# ecohydro-mega-shield.net
KiCad netlist of a schematic drawn in EAGLE
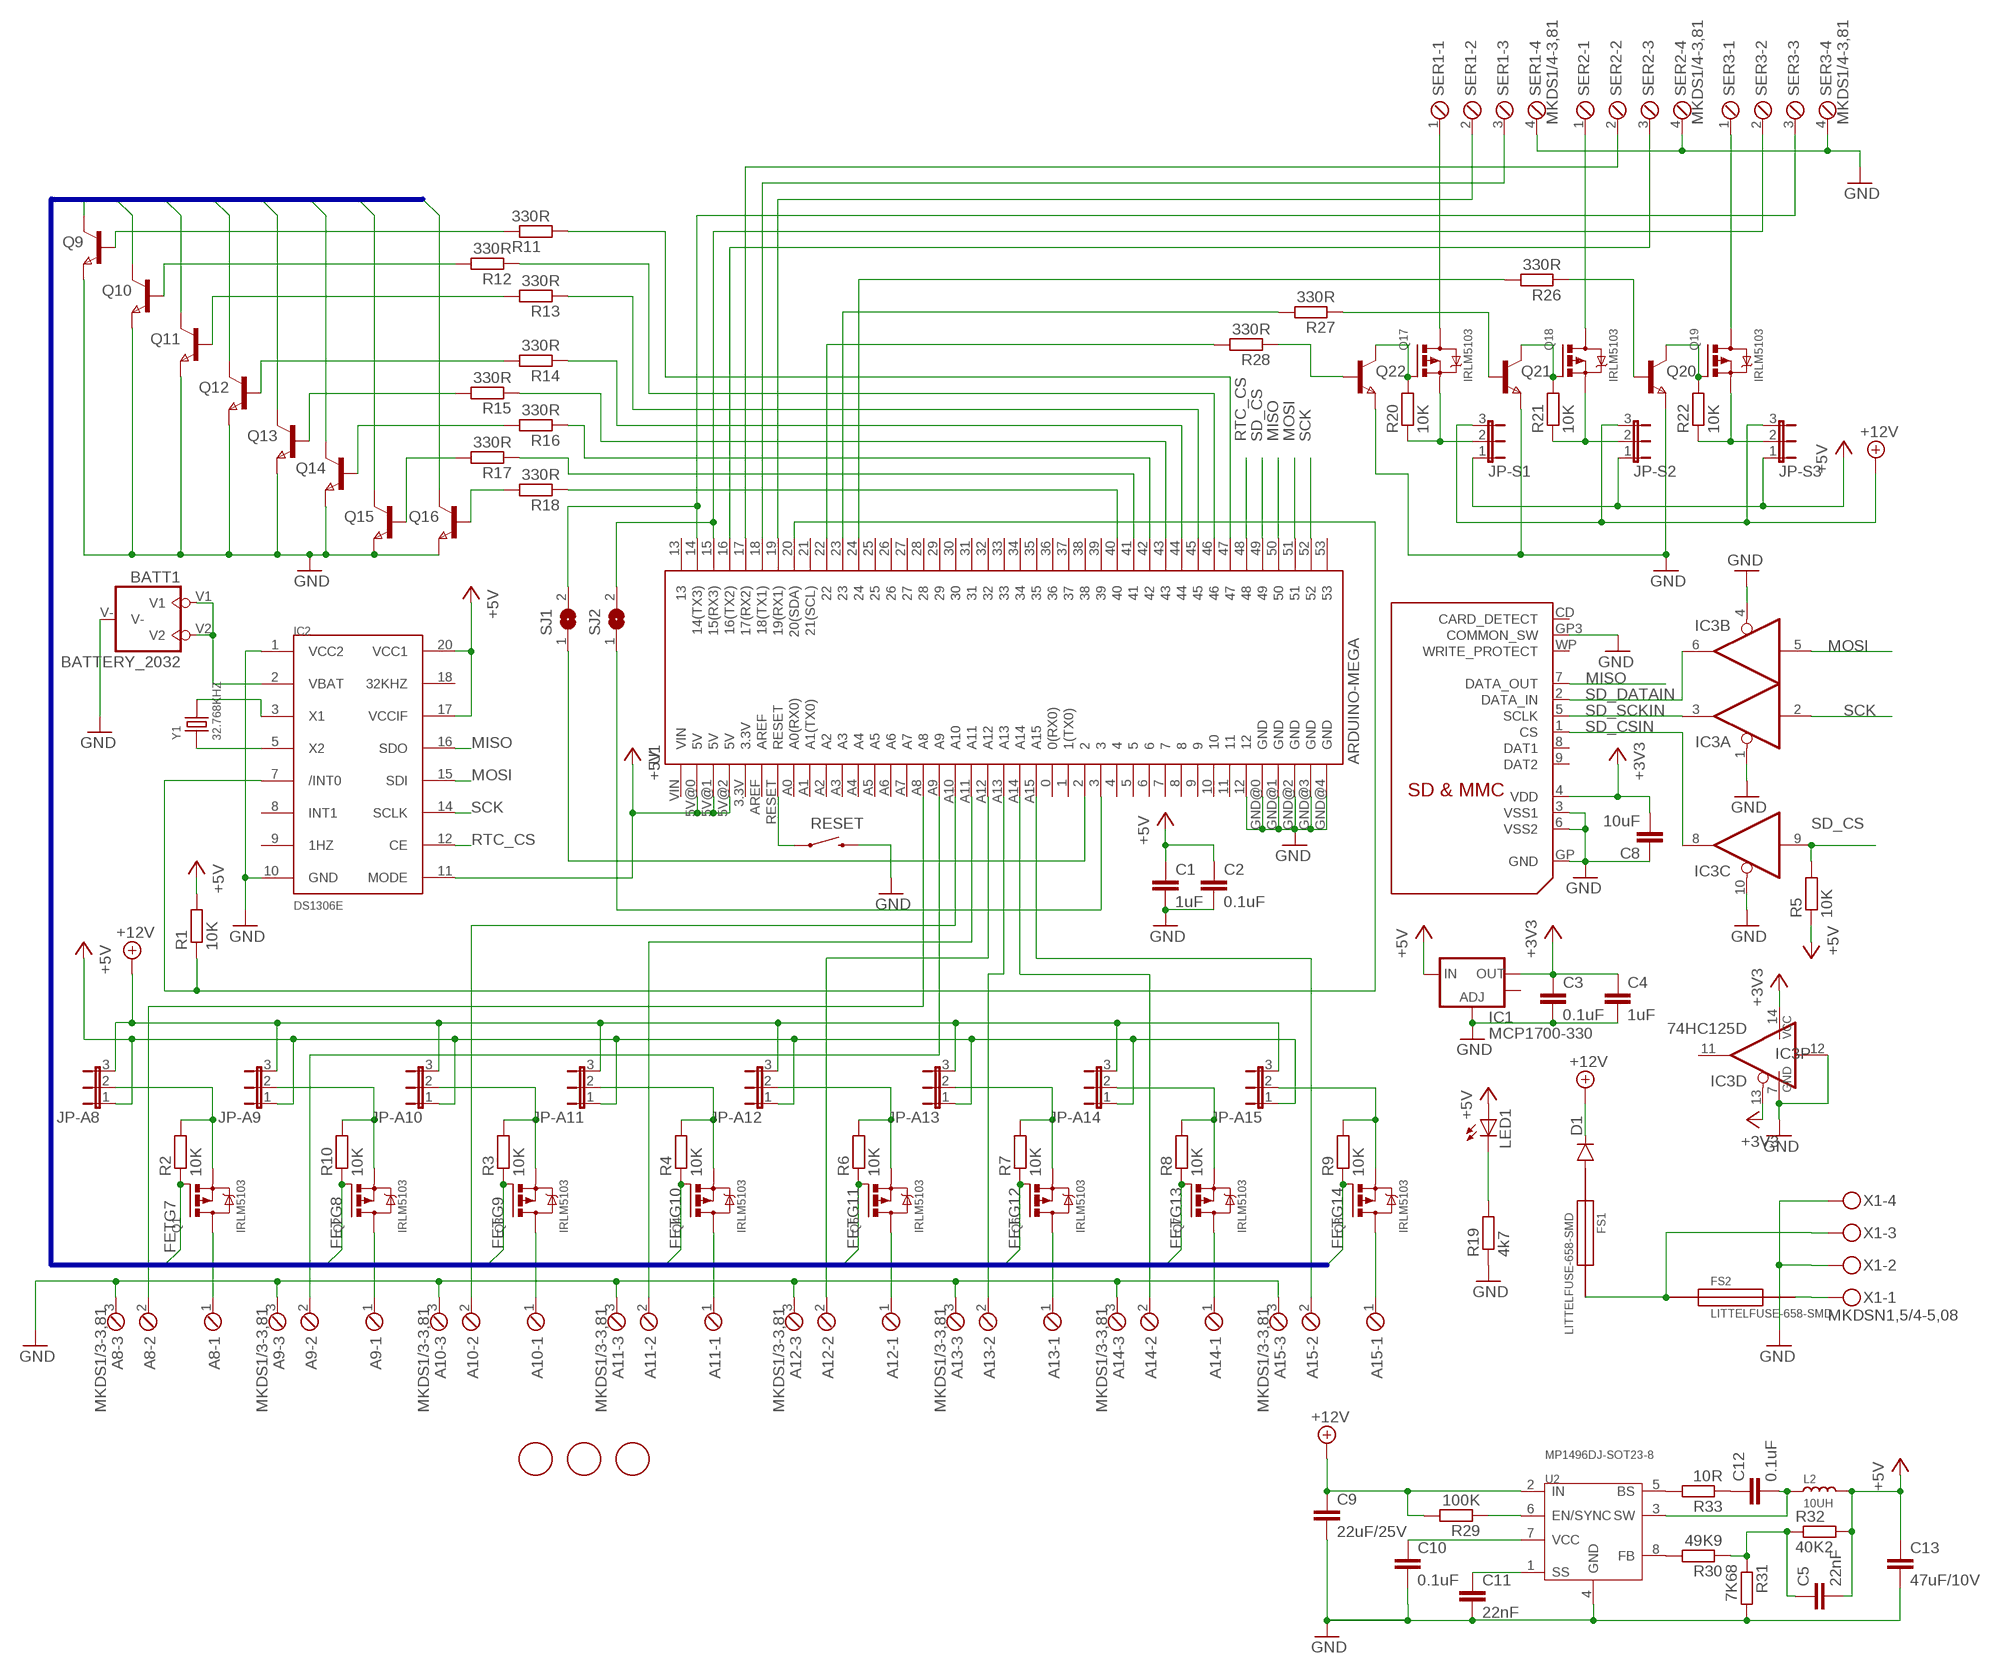
[diagram p0: schematic, sheet 1]

(export (version "E")
  (design (tool "Eeschema 10.0.6"))
  (components
    (comp (ref "A8")
      (value "MKDS1/3-3,81")
      (footprint "eagle-import:3POL381")
      (libsource (lib "eagle-import") (part "MKDS1/3-3,81"))
    )
    (comp (ref "A9")
      (value "MKDS1/3-3,81")
      (footprint "eagle-import:3POL381")
      (libsource (lib "eagle-import") (part "MKDS1/3-3,81"))
    )
    (comp (ref "A10")
      (value "MKDS1/3-3,81")
      (footprint "eagle-import:3POL381")
      (libsource (lib "eagle-import") (part "MKDS1/3-3,81"))
    )
    (comp (ref "A11")
      (value "MKDS1/3-3,81")
      (footprint "eagle-import:3POL381")
      (libsource (lib "eagle-import") (part "MKDS1/3-3,81"))
    )
    (comp (ref "A12")
      (value "MKDS1/3-3,81")
      (footprint "eagle-import:3POL381")
      (libsource (lib "eagle-import") (part "MKDS1/3-3,81"))
    )
    (comp (ref "A13")
      (value "MKDS1/3-3,81")
      (footprint "eagle-import:3POL381")
      (libsource (lib "eagle-import") (part "MKDS1/3-3,81"))
    )
    (comp (ref "A14")
      (value "MKDS1/3-3,81")
      (footprint "eagle-import:3POL381")
      (libsource (lib "eagle-import") (part "MKDS1/3-3,81"))
    )
    (comp (ref "A15")
      (value "MKDS1/3-3,81")
      (footprint "eagle-import:3POL381")
      (libsource (lib "eagle-import") (part "MKDS1/3-3,81"))
    )
    (comp (ref "BATT1")
      (value "BATTERY_2032")
      (footprint "eagle-import:BATT2032")
      (libsource (lib "eagle-import") (part "BATTERY_2032"))
    )
    (comp (ref "C1")
      (value "1uF")
      (footprint "eagle-import:C0805K")
      (libsource (lib "eagle-import") (part "C-EUC0805K"))
    )
    (comp (ref "C2")
      (value "0.1uF")
      (footprint "eagle-import:C0805K")
      (libsource (lib "eagle-import") (part "C-EUC0805K"))
    )
    (comp (ref "C3")
      (value "0.1uF")
      (footprint "eagle-import:C0805K")
      (libsource (lib "eagle-import") (part "C-EUC0805K"))
    )
    (comp (ref "C4")
      (value "1uF")
      (footprint "eagle-import:C0805K")
      (libsource (lib "eagle-import") (part "C-EUC0805K"))
    )
    (comp (ref "C5")
      (value "22nF")
      (footprint "eagle-import:C0805K")
      (libsource (lib "eagle-import") (part "C-EUC0805K"))
    )
    (comp (ref "C8")
      (value "10uF")
      (footprint "eagle-import:C0805K")
      (libsource (lib "eagle-import") (part "C-EUC0805K"))
    )
    (comp (ref "C9")
      (value "22uF/25V")
      (footprint "eagle-import:C0805K")
      (libsource (lib "eagle-import") (part "C-EUC0805K"))
    )
    (comp (ref "C10")
      (value "0.1uF")
      (footprint "eagle-import:C0805K")
      (libsource (lib "eagle-import") (part "C-EUC0805K"))
    )
    (comp (ref "C11")
      (value "22nF")
      (footprint "eagle-import:C0805K")
      (libsource (lib "eagle-import") (part "C-EUC0805K"))
    )
    (comp (ref "C12")
      (value "0.1uF")
      (footprint "eagle-import:C0805K")
      (libsource (lib "eagle-import") (part "C-EUC0805K"))
    )
    (comp (ref "C13")
      (value "47uF/10V")
      (footprint "eagle-import:C0805K")
      (libsource (lib "eagle-import") (part "C-EUC0805K"))
    )
    (comp (ref "D1")
      (value "DIODESMA")
      (footprint "eagle-import:SMA-DIODE")
      (libsource (lib "eagle-import") (part "DIODESMA"))
    )
    (comp (ref "FS1")
      (value "LITTELFUSE-658-SMD")
      (footprint "eagle-import:LITTELFUSE-658-SMD")
      (libsource (lib "eagle-import") (part "LITTELFUSE-658-SMD"))
    )
    (comp (ref "FS2")
      (value "LITTELFUSE-658-SMD")
      (footprint "eagle-import:LITTELFUSE-658-SMD")
      (libsource (lib "eagle-import") (part "LITTELFUSE-658-SMD"))
    )
    (comp (ref "IC1")
      (value "MCP1700-330")
      (footprint "eagle-import:SOT223")
      (libsource (lib "eagle-import") (part "V_REG_LM1117SOT223"))
    )
    (comp (ref "IC2")
      (value "DS1306E")
      (footprint "eagle-import:SSOP20")
      (libsource (lib "eagle-import") (part "DS1306E"))
    )
    (comp (ref "IC3")
      (value "74HC125D")
      (footprint "eagle-import:SO14")
      (fields (field (name "DIGIKEY") "568-1392-2-ND "))
      (libsource (lib "eagle-import") (part "74125DHC"))
    )
    (comp (ref "JP-A8")
      (value "JP2E")
      (footprint "eagle-import:JP2")
      (libsource (lib "eagle-import") (part "JP2E"))
    )
    (comp (ref "JP-A9")
      (value "JP2E")
      (footprint "eagle-import:JP2")
      (libsource (lib "eagle-import") (part "JP2E"))
    )
    (comp (ref "JP-A10")
      (value "JP2E")
      (footprint "eagle-import:JP2")
      (libsource (lib "eagle-import") (part "JP2E"))
    )
    (comp (ref "JP-A11")
      (value "JP2E")
      (footprint "eagle-import:JP2")
      (libsource (lib "eagle-import") (part "JP2E"))
    )
    (comp (ref "JP-A12")
      (value "JP2E")
      (footprint "eagle-import:JP2")
      (libsource (lib "eagle-import") (part "JP2E"))
    )
    (comp (ref "JP-A13")
      (value "JP2E")
      (footprint "eagle-import:JP2")
      (libsource (lib "eagle-import") (part "JP2E"))
    )
    (comp (ref "JP-A14")
      (value "JP2E")
      (footprint "eagle-import:JP2")
      (libsource (lib "eagle-import") (part "JP2E"))
    )
    (comp (ref "JP-A15")
      (value "JP2E")
      (footprint "eagle-import:JP2")
      (libsource (lib "eagle-import") (part "JP2E"))
    )
    (comp (ref "JP-S1")
      (value "JP2E")
      (footprint "eagle-import:JP2")
      (libsource (lib "eagle-import") (part "JP2E"))
    )
    (comp (ref "JP-S2")
      (value "JP2E")
      (footprint "eagle-import:JP2")
      (libsource (lib "eagle-import") (part "JP2E"))
    )
    (comp (ref "JP-S3")
      (value "JP2E")
      (footprint "eagle-import:JP2")
      (libsource (lib "eagle-import") (part "JP2E"))
    )
    (comp (ref "L2")
      (value "10UH")
      (footprint "eagle-import:SMD-2P-L6.0XW6.0XH3.0MM")
      (fields (field (name "MPN") "CSAB0630-100M"))
      (libsource (lib "eagle-import") (part "SMD-INDUCTOR-10UH-20%(2P-6X6MM)'0630'"))
    )
    (comp (ref "LED1")
      (value "LED1206")
      (footprint "eagle-import:LED-1206")
      (libsource (lib "eagle-import") (part "LED1206"))
    )
    (comp (ref "Q1")
      (value "IRLM5103")
      (footprint "eagle-import:MICRO3")
      (libsource (lib "eagle-import") (part "IRLM5103"))
    )
    (comp (ref "Q2")
      (value "IRLM5103")
      (footprint "eagle-import:MICRO3")
      (libsource (lib "eagle-import") (part "IRLM5103"))
    )
    (comp (ref "Q3")
      (value "IRLM5103")
      (footprint "eagle-import:MICRO3")
      (libsource (lib "eagle-import") (part "IRLM5103"))
    )
    (comp (ref "Q4")
      (value "IRLM5103")
      (footprint "eagle-import:MICRO3")
      (libsource (lib "eagle-import") (part "IRLM5103"))
    )
    (comp (ref "Q5")
      (value "IRLM5103")
      (footprint "eagle-import:MICRO3")
      (libsource (lib "eagle-import") (part "IRLM5103"))
    )
    (comp (ref "Q6")
      (value "IRLM5103")
      (footprint "eagle-import:MICRO3")
      (libsource (lib "eagle-import") (part "IRLM5103"))
    )
    (comp (ref "Q7")
      (value "IRLM5103")
      (footprint "eagle-import:MICRO3")
      (libsource (lib "eagle-import") (part "IRLM5103"))
    )
    (comp (ref "Q8")
      (value "IRLM5103")
      (footprint "eagle-import:MICRO3")
      (libsource (lib "eagle-import") (part "IRLM5103"))
    )
    (comp (ref "Q9")
      (value "PBSS4021NT,215")
      (footprint "eagle-import:SOT23")
      (libsource (lib "eagle-import") (part "PBSS4021NT,215"))
    )
    (comp (ref "Q10")
      (value "PBSS4021NT,215")
      (footprint "eagle-import:SOT23")
      (libsource (lib "eagle-import") (part "PBSS4021NT,215"))
    )
    (comp (ref "Q11")
      (value "PBSS4021NT,215")
      (footprint "eagle-import:SOT23")
      (libsource (lib "eagle-import") (part "PBSS4021NT,215"))
    )
    (comp (ref "Q12")
      (value "PBSS4021NT,215")
      (footprint "eagle-import:SOT23")
      (libsource (lib "eagle-import") (part "PBSS4021NT,215"))
    )
    (comp (ref "Q13")
      (value "PBSS4021NT,215")
      (footprint "eagle-import:SOT23")
      (libsource (lib "eagle-import") (part "PBSS4021NT,215"))
    )
    (comp (ref "Q14")
      (value "PBSS4021NT,215")
      (footprint "eagle-import:SOT23")
      (libsource (lib "eagle-import") (part "PBSS4021NT,215"))
    )
    (comp (ref "Q15")
      (value "PBSS4021NT,215")
      (footprint "eagle-import:SOT23")
      (libsource (lib "eagle-import") (part "PBSS4021NT,215"))
    )
    (comp (ref "Q16")
      (value "PBSS4021NT,215")
      (footprint "eagle-import:SOT23")
      (libsource (lib "eagle-import") (part "PBSS4021NT,215"))
    )
    (comp (ref "Q17")
      (value "IRLM5103")
      (footprint "eagle-import:MICRO3")
      (libsource (lib "eagle-import") (part "IRLM5103"))
    )
    (comp (ref "Q18")
      (value "IRLM5103")
      (footprint "eagle-import:MICRO3")
      (libsource (lib "eagle-import") (part "IRLM5103"))
    )
    (comp (ref "Q19")
      (value "IRLM5103")
      (footprint "eagle-import:MICRO3")
      (libsource (lib "eagle-import") (part "IRLM5103"))
    )
    (comp (ref "Q20")
      (value "PBSS4021NT,215")
      (footprint "eagle-import:SOT23")
      (libsource (lib "eagle-import") (part "PBSS4021NT,215"))
    )
    (comp (ref "Q21")
      (value "PBSS4021NT,215")
      (footprint "eagle-import:SOT23")
      (libsource (lib "eagle-import") (part "PBSS4021NT,215"))
    )
    (comp (ref "Q22")
      (value "PBSS4021NT,215")
      (footprint "eagle-import:SOT23")
      (libsource (lib "eagle-import") (part "PBSS4021NT,215"))
    )
    (comp (ref "R1")
      (value "10K")
      (footprint "eagle-import:M0805")
      (libsource (lib "eagle-import") (part "rcl_R-EU_M0805"))
    )
    (comp (ref "R2")
      (value "10K")
      (footprint "eagle-import:M0805")
      (libsource (lib "eagle-import") (part "rcl_R-EU_M0805"))
    )
    (comp (ref "R3")
      (value "10K")
      (footprint "eagle-import:M0805")
      (libsource (lib "eagle-import") (part "rcl_R-EU_M0805"))
    )
    (comp (ref "R4")
      (value "10K")
      (footprint "eagle-import:M0805")
      (libsource (lib "eagle-import") (part "rcl_R-EU_M0805"))
    )
    (comp (ref "R5")
      (value "10K")
      (footprint "eagle-import:M0805")
      (libsource (lib "eagle-import") (part "rcl_R-EU_M0805"))
    )
    (comp (ref "R6")
      (value "10K")
      (footprint "eagle-import:M0805")
      (libsource (lib "eagle-import") (part "rcl_R-EU_M0805"))
    )
    (comp (ref "R7")
      (value "10K")
      (footprint "eagle-import:M0805")
      (libsource (lib "eagle-import") (part "rcl_R-EU_M0805"))
    )
    (comp (ref "R8")
      (value "10K")
      (footprint "eagle-import:M0805")
      (libsource (lib "eagle-import") (part "rcl_R-EU_M0805"))
    )
    (comp (ref "R9")
      (value "10K")
      (footprint "eagle-import:M0805")
      (libsource (lib "eagle-import") (part "rcl_R-EU_M0805"))
    )
    (comp (ref "R10")
      (value "10K")
      (footprint "eagle-import:M0805")
      (libsource (lib "eagle-import") (part "rcl_R-EU_M0805"))
    )
    (comp (ref "R11")
      (value "330R")
      (footprint "eagle-import:M0805")
      (libsource (lib "eagle-import") (part "rcl_R-EU_M0805"))
    )
    (comp (ref "R12")
      (value "330R")
      (footprint "eagle-import:M0805")
      (libsource (lib "eagle-import") (part "rcl_R-EU_M0805"))
    )
    (comp (ref "R13")
      (value "330R")
      (footprint "eagle-import:M0805")
      (libsource (lib "eagle-import") (part "rcl_R-EU_M0805"))
    )
    (comp (ref "R14")
      (value "330R")
      (footprint "eagle-import:M0805")
      (libsource (lib "eagle-import") (part "rcl_R-EU_M0805"))
    )
    (comp (ref "R15")
      (value "330R")
      (footprint "eagle-import:M0805")
      (libsource (lib "eagle-import") (part "rcl_R-EU_M0805"))
    )
    (comp (ref "R16")
      (value "330R")
      (footprint "eagle-import:M0805")
      (libsource (lib "eagle-import") (part "rcl_R-EU_M0805"))
    )
    (comp (ref "R17")
      (value "330R")
      (footprint "eagle-import:M0805")
      (libsource (lib "eagle-import") (part "rcl_R-EU_M0805"))
    )
    (comp (ref "R18")
      (value "330R")
      (footprint "eagle-import:M0805")
      (libsource (lib "eagle-import") (part "rcl_R-EU_M0805"))
    )
    (comp (ref "R19")
      (value "4k7")
      (footprint "eagle-import:R0805")
      (libsource (lib "eagle-import") (part "R-EU_R0805"))
    )
    (comp (ref "R20")
      (value "10K")
      (footprint "eagle-import:M0805")
      (libsource (lib "eagle-import") (part "rcl_R-EU_M0805"))
    )
    (comp (ref "R21")
      (value "10K")
      (footprint "eagle-import:M0805")
      (libsource (lib "eagle-import") (part "rcl_R-EU_M0805"))
    )
    (comp (ref "R22")
      (value "10K")
      (footprint "eagle-import:M0805")
      (libsource (lib "eagle-import") (part "rcl_R-EU_M0805"))
    )
    (comp (ref "R26")
      (value "330R")
      (footprint "eagle-import:M0805")
      (libsource (lib "eagle-import") (part "rcl_R-EU_M0805"))
    )
    (comp (ref "R27")
      (value "330R")
      (footprint "eagle-import:M0805")
      (libsource (lib "eagle-import") (part "rcl_R-EU_M0805"))
    )
    (comp (ref "R28")
      (value "330R")
      (footprint "eagle-import:M0805")
      (libsource (lib "eagle-import") (part "rcl_R-EU_M0805"))
    )
    (comp (ref "R29")
      (value "100K")
      (footprint "eagle-import:M0805")
      (libsource (lib "eagle-import") (part "rcl_R-EU_M0805"))
    )
    (comp (ref "R30")
      (value "49K9")
      (footprint "eagle-import:M0805")
      (libsource (lib "eagle-import") (part "rcl_R-EU_M0805"))
    )
    (comp (ref "R31")
      (value "7K68")
      (footprint "eagle-import:M0805")
      (libsource (lib "eagle-import") (part "rcl_R-EU_M0805"))
    )
    (comp (ref "R32")
      (value "40K2")
      (footprint "eagle-import:M0805")
      (libsource (lib "eagle-import") (part "rcl_R-EU_M0805"))
    )
    (comp (ref "R33")
      (value "10R")
      (footprint "eagle-import:M0805")
      (libsource (lib "eagle-import") (part "rcl_R-EU_M0805"))
    )
    (comp (ref "RESET")
      (value "SWITCH-MOMENTARY-2-SMD-1101NE")
      (footprint "eagle-import:TACTILE-SWITCH-1101NE")
      (libsource (lib "eagle-import") (part "SWITCH-MOMENTARY-2-SMD-1101NE"))
    )
    (comp (ref "SER1")
      (value "MKDS1/4-3,81")
      (footprint "eagle-import:4POL381")
      (libsource (lib "eagle-import") (part "MKDS1/4-3,81"))
    )
    (comp (ref "SER2")
      (value "MKDS1/4-3,81")
      (footprint "eagle-import:4POL381")
      (libsource (lib "eagle-import") (part "MKDS1/4-3,81"))
    )
    (comp (ref "SER3")
      (value "MKDS1/4-3,81")
      (footprint "eagle-import:4POL381")
      (libsource (lib "eagle-import") (part "MKDS1/4-3,81"))
    )
    (comp (ref "SJ1") (value "SJ") (footprint "eagle-import:SJ") (libsource (lib "eagle-import") (part "SJ")))
    (comp (ref "SJ2") (value "SJ") (footprint "eagle-import:SJ") (libsource (lib "eagle-import") (part "SJ")))
    (comp (ref "U$1")
      (value "SDMMC06132")
      (footprint "eagle-import:06132")
      (libsource (lib "eagle-import") (part "SDMMC06132"))
    )
    (comp (ref "U$2")
      (value "FIDUCIAL")
      (footprint "eagle-import:FIDUCIAL_1MM")
      (libsource (lib "eagle-import") (part "FIDUCIAL"))
    )
    (comp (ref "U$3")
      (value "FIDUCIAL")
      (footprint "eagle-import:FIDUCIAL_1MM")
      (libsource (lib "eagle-import") (part "FIDUCIAL"))
    )
    (comp (ref "U$4")
      (value "FIDUCIAL")
      (footprint "eagle-import:FIDUCIAL_1MM")
      (libsource (lib "eagle-import") (part "FIDUCIAL"))
    )
    (comp (ref "U1")
      (value "ARDUINO-MEGA")
      (footprint "eagle-import:ARDUINO_MEGA_NOHOLES")
      (libsource (lib "eagle-import") (part "ARDUINO-MEGA"))
    )
    (comp (ref "U2")
      (value "MP1496DJ-SOT23-8")
      (footprint "eagle-import:SOT-23-8")
      (fields (field (name "MPN") "MP1496DJ"))
      (libsource (lib "eagle-import") (part "PMIC-MP1496DJ(SOT23-8)"))
    )
    (comp (ref "X1")
      (value "MKDSN1,5/4-5,08")
      (footprint "eagle-import:MKDSN1,5_4-5,08")
      (libsource (lib "eagle-import") (part "MKDSN1,5/4-5,08"))
    )
    (comp (ref "Y1")
      (value "32.768KHZ")
      (footprint "eagle-import:X2-SMD-L2.0X1.2X0.55MM")
      (fields (field (name "MPN") "FC-12M"))
      (libsource (lib "eagle-import") (part "SMD-CRYSTAL-32.768KHZ-12.5PF-20PPM-90K(2P-L2.0X1.2MM)"))
    )
  )
  (nets
    (net (code "1") (name "+3V3") (class "Default")
      (node (ref "C3") (pin "1") (pinfunction "1_1") (pintype "passive"))
      (node (ref "C4") (pin "1") (pinfunction "1_1") (pintype "passive"))
      (node (ref "C8") (pin "2") (pinfunction "2_2") (pintype "passive"))
      (node (ref "IC1") (pin "2") (pinfunction "OUT_2") (pintype "output"))
      (node (ref "IC3") (pin "13") (pinfunction "OE_13") (pintype "input"))
      (node (ref "IC3") (pin "14") (pinfunction "VCC_14") (pintype "power_in"))
      (node (ref "U$1") (pin "4") (pinfunction "VDD_4") (pintype "power_in"))
    )
    (net (code "2") (name "+5V") (class "Default")
      (node (ref "C1") (pin "1") (pinfunction "1_1") (pintype "passive"))
      (node (ref "C13") (pin "1") (pinfunction "1_1") (pintype "passive"))
      (node (ref "C2") (pin "1") (pinfunction "1_1") (pintype "passive"))
      (node (ref "C5") (pin "2") (pinfunction "2_2") (pintype "passive"))
      (node (ref "IC1") (pin "3") (pinfunction "IN_3") (pintype "input"))
      (node (ref "IC2") (pin "11") (pinfunction "MODE_11") (pintype "input"))
      (node (ref "IC2") (pin "17") (pinfunction "VCCIF_17") (pintype "power_in"))
      (node (ref "IC2") (pin "20") (pinfunction "VCC1_20") (pintype "power_in"))
      (node (ref "JP-A10") (pin "1") (pinfunction "1_1") (pintype "passive"))
      (node (ref "JP-A11") (pin "1") (pinfunction "1_1") (pintype "passive"))
      (node (ref "JP-A12") (pin "1") (pinfunction "1_1") (pintype "passive"))
      (node (ref "JP-A13") (pin "1") (pinfunction "1_1") (pintype "passive"))
      (node (ref "JP-A14") (pin "1") (pinfunction "1_1") (pintype "passive"))
      (node (ref "JP-A15") (pin "1") (pinfunction "1_1") (pintype "passive"))
      (node (ref "JP-A8") (pin "1") (pinfunction "1_1") (pintype "passive"))
      (node (ref "JP-A9") (pin "1") (pinfunction "1_1") (pintype "passive"))
      (node (ref "JP-S1") (pin "1") (pinfunction "1_1") (pintype "passive"))
      (node (ref "JP-S2") (pin "1") (pinfunction "1_1") (pintype "passive"))
      (node (ref "JP-S3") (pin "1") (pinfunction "1_1") (pintype "passive"))
      (node (ref "L2") (pin "2") (pinfunction "2_2") (pintype "passive"))
      (node (ref "LED1") (pin "A") (pinfunction "A_A") (pintype "passive"))
      (node (ref "R1") (pin "2") (pinfunction "2_2") (pintype "passive"))
      (node (ref "R32") (pin "2") (pinfunction "2_2") (pintype "passive"))
      (node (ref "R5") (pin "1") (pinfunction "1_1") (pintype "passive"))
      (node (ref "U1") (pin "5V@0") (pinfunction "5V_5V@0") (pintype "bidirectional"))
      (node (ref "U1") (pin "5V@1") (pinfunction "5V_5V@1") (pintype "bidirectional"))
      (node (ref "U1") (pin "5V@2") (pinfunction "5V_5V@2") (pintype "bidirectional"))
    )
    (net (code "3") (name "+12V") (class "Default")
      (node (ref "C9") (pin "1") (pinfunction "1_1") (pintype "passive"))
      (node (ref "D1") (pin "C") (pinfunction "C_C") (pintype "passive"))
      (node (ref "JP-A10") (pin "3") (pinfunction "3_3") (pintype "passive"))
      (node (ref "JP-A11") (pin "3") (pinfunction "3_3") (pintype "passive"))
      (node (ref "JP-A12") (pin "3") (pinfunction "3_3") (pintype "passive"))
      (node (ref "JP-A13") (pin "3") (pinfunction "3_3") (pintype "passive"))
      (node (ref "JP-A14") (pin "3") (pinfunction "3_3") (pintype "passive"))
      (node (ref "JP-A15") (pin "3") (pinfunction "3_3") (pintype "passive"))
      (node (ref "JP-A8") (pin "3") (pinfunction "3_3") (pintype "passive"))
      (node (ref "JP-A9") (pin "3") (pinfunction "3_3") (pintype "passive"))
      (node (ref "JP-S1") (pin "3") (pinfunction "3_3") (pintype "passive"))
      (node (ref "JP-S2") (pin "3") (pinfunction "3_3") (pintype "passive"))
      (node (ref "JP-S3") (pin "3") (pinfunction "3_3") (pintype "passive"))
      (node (ref "R29") (pin "2") (pinfunction "2_2") (pintype "passive"))
      (node (ref "U2") (pin "2") (pinfunction "IN_2") (pintype "bidirectional"))
    )
    (net (code "4") (name "/FETG7") (class "Default")
      (node (ref "Q1") (pin "1") (pinfunction "G_1") (pintype "passive"))
      (node (ref "Q16") (pin "3") (pinfunction "C_3") (pintype "passive"))
      (node (ref "R2") (pin "1") (pinfunction "1_1") (pintype "passive"))
    )
    (net (code "5") (name "/FETG8") (class "Default")
      (node (ref "Q15") (pin "3") (pinfunction "C_3") (pintype "passive"))
      (node (ref "Q2") (pin "1") (pinfunction "G_1") (pintype "passive"))
      (node (ref "R10") (pin "1") (pinfunction "1_1") (pintype "passive"))
    )
    (net (code "6") (name "/FETG9") (class "Default")
      (node (ref "Q14") (pin "3") (pinfunction "C_3") (pintype "passive"))
      (node (ref "Q3") (pin "1") (pinfunction "G_1") (pintype "passive"))
      (node (ref "R3") (pin "1") (pinfunction "1_1") (pintype "passive"))
    )
    (net (code "7") (name "/FETG10") (class "Default")
      (node (ref "Q13") (pin "3") (pinfunction "C_3") (pintype "passive"))
      (node (ref "Q4") (pin "1") (pinfunction "G_1") (pintype "passive"))
      (node (ref "R4") (pin "1") (pinfunction "1_1") (pintype "passive"))
    )
    (net (code "8") (name "/FETG11") (class "Default")
      (node (ref "Q12") (pin "3") (pinfunction "C_3") (pintype "passive"))
      (node (ref "Q5") (pin "1") (pinfunction "G_1") (pintype "passive"))
      (node (ref "R6") (pin "1") (pinfunction "1_1") (pintype "passive"))
    )
    (net (code "9") (name "/FETG12") (class "Default")
      (node (ref "Q11") (pin "3") (pinfunction "C_3") (pintype "passive"))
      (node (ref "Q6") (pin "1") (pinfunction "G_1") (pintype "passive"))
      (node (ref "R7") (pin "1") (pinfunction "1_1") (pintype "passive"))
    )
    (net (code "10") (name "/FETG13") (class "Default")
      (node (ref "Q10") (pin "3") (pinfunction "C_3") (pintype "passive"))
      (node (ref "Q7") (pin "1") (pinfunction "G_1") (pintype "passive"))
      (node (ref "R8") (pin "1") (pinfunction "1_1") (pintype "passive"))
    )
    (net (code "11") (name "/FETG14") (class "Default")
      (node (ref "Q8") (pin "1") (pinfunction "G_1") (pintype "passive"))
      (node (ref "Q9") (pin "3") (pinfunction "C_3") (pintype "passive"))
      (node (ref "R9") (pin "1") (pinfunction "1_1") (pintype "passive"))
    )
    (net (code "12") (name "/MISO") (class "Default")
      (node (ref "IC2") (pin "16") (pinfunction "SDO_16") (pintype "output"))
      (node (ref "U$1") (pin "7") (pinfunction "DATA_OUT_7") (pintype "output"))
      (node (ref "U1") (pin "50") (pinfunction "50_50") (pintype "bidirectional"))
    )
    (net (code "13") (name "/MOSI") (class "Default")
      (node (ref "IC2") (pin "15") (pinfunction "SDI_15") (pintype "input"))
      (node (ref "IC3") (pin "5") (pinfunction "I_5") (pintype "input"))
      (node (ref "U1") (pin "51") (pinfunction "51_51") (pintype "bidirectional"))
    )
    (net (code "14") (name "/RTC_CS") (class "Default")
      (node (ref "IC2") (pin "12") (pinfunction "CE_12") (pintype "input"))
      (node (ref "U1") (pin "48") (pinfunction "48_48") (pintype "bidirectional"))
    )
    (net (code "15") (name "/SCK") (class "Default")
      (node (ref "IC2") (pin "14") (pinfunction "SCLK_14") (pintype "input"))
      (node (ref "IC3") (pin "2") (pinfunction "I_2") (pintype "input"))
      (node (ref "U1") (pin "52") (pinfunction "52_52") (pintype "bidirectional"))
    )
    (net (code "16") (name "/SD_CS") (class "Default")
      (node (ref "IC3") (pin "9") (pinfunction "I_9") (pintype "input"))
      (node (ref "R5") (pin "2") (pinfunction "2_2") (pintype "passive"))
      (node (ref "U1") (pin "49") (pinfunction "49_49") (pintype "bidirectional"))
    )
    (net (code "17") (name "/SD_CSIN") (class "Default")
      (node (ref "IC3") (pin "8") (pinfunction "O_8") (pintype "tri_state"))
      (node (ref "U$1") (pin "1") (pinfunction "CS_1") (pintype "input"))
    )
    (net (code "18") (name "/SD_DATAIN") (class "Default")
      (node (ref "IC3") (pin "6") (pinfunction "O_6") (pintype "tri_state"))
      (node (ref "U$1") (pin "2") (pinfunction "DATA_IN_2") (pintype "input"))
    )
    (net (code "19") (name "/SD_SCKIN") (class "Default")
      (node (ref "IC3") (pin "3") (pinfunction "O_3") (pintype "tri_state"))
      (node (ref "U$1") (pin "5") (pinfunction "SCLK_5") (pintype "input"))
    )
    (net (code "20") (name "GND") (class "Default")
      (node (ref "A10") (pin "3") (pinfunction "1_3") (pintype "passive"))
      (node (ref "A11") (pin "3") (pinfunction "1_3") (pintype "passive"))
      (node (ref "A12") (pin "3") (pinfunction "1_3") (pintype "passive"))
      (node (ref "A13") (pin "3") (pinfunction "1_3") (pintype "passive"))
      (node (ref "A14") (pin "3") (pinfunction "1_3") (pintype "passive"))
      (node (ref "A15") (pin "3") (pinfunction "1_3") (pintype "passive"))
      (node (ref "A8") (pin "3") (pinfunction "1_3") (pintype "passive"))
      (node (ref "A9") (pin "3") (pinfunction "1_3") (pintype "passive"))
      (node (ref "BATT1") (pin "V-") (pinfunction "V-_V-") (pintype "power_in"))
      (node (ref "C1") (pin "2") (pinfunction "2_2") (pintype "passive"))
      (node (ref "C10") (pin "2") (pinfunction "2_2") (pintype "passive"))
      (node (ref "C11") (pin "2") (pinfunction "2_2") (pintype "passive"))
      (node (ref "C13") (pin "2") (pinfunction "2_2") (pintype "passive"))
      (node (ref "C2") (pin "2") (pinfunction "2_2") (pintype "passive"))
      (node (ref "C3") (pin "2") (pinfunction "2_2") (pintype "passive"))
      (node (ref "C4") (pin "2") (pinfunction "2_2") (pintype "passive"))
      (node (ref "C8") (pin "1") (pinfunction "1_1") (pintype "passive"))
      (node (ref "C9") (pin "2") (pinfunction "2_2") (pintype "passive"))
      (node (ref "IC1") (pin "1") (pinfunction "ADJ_1") (pintype "input"))
      (node (ref "IC2") (pin "1") (pinfunction "VCC2_1") (pintype "power_in"))
      (node (ref "IC2") (pin "10") (pinfunction "GND_10") (pintype "power_in"))
      (node (ref "IC3") (pin "1") (pinfunction "OE_1") (pintype "input"))
      (node (ref "IC3") (pin "10") (pinfunction "OE_10") (pintype "input"))
      (node (ref "IC3") (pin "12") (pinfunction "I_12") (pintype "input"))
      (node (ref "IC3") (pin "4") (pinfunction "OE_4") (pintype "input"))
      (node (ref "IC3") (pin "7") (pinfunction "GND_7") (pintype "power_in"))
      (node (ref "Q10") (pin "2") (pinfunction "E_2") (pintype "passive"))
      (node (ref "Q11") (pin "2") (pinfunction "E_2") (pintype "passive"))
      (node (ref "Q12") (pin "2") (pinfunction "E_2") (pintype "passive"))
      (node (ref "Q13") (pin "2") (pinfunction "E_2") (pintype "passive"))
      (node (ref "Q14") (pin "2") (pinfunction "E_2") (pintype "passive"))
      (node (ref "Q15") (pin "2") (pinfunction "E_2") (pintype "passive"))
      (node (ref "Q16") (pin "2") (pinfunction "E_2") (pintype "passive"))
      (node (ref "Q20") (pin "2") (pinfunction "E_2") (pintype "passive"))
      (node (ref "Q21") (pin "2") (pinfunction "E_2") (pintype "passive"))
      (node (ref "Q22") (pin "2") (pinfunction "E_2") (pintype "passive"))
      (node (ref "Q9") (pin "2") (pinfunction "E_2") (pintype "passive"))
      (node (ref "R19") (pin "1") (pinfunction "1_1") (pintype "passive"))
      (node (ref "R31") (pin "2") (pinfunction "2_2") (pintype "passive"))
      (node (ref "RESET") (pin "P$2") (pinfunction "2_P$2") (pintype "passive"))
      (node (ref "SER1") (pin "4") (pinfunction "1_4") (pintype "passive"))
      (node (ref "SER2") (pin "4") (pinfunction "1_4") (pintype "passive"))
      (node (ref "SER3") (pin "4") (pinfunction "1_4") (pintype "passive"))
      (node (ref "U$1") (pin "3") (pinfunction "VSS1_3") (pintype "power_in"))
      (node (ref "U$1") (pin "6") (pinfunction "VSS2_6") (pintype "power_in"))
      (node (ref "U$1") (pin "GP") (pinfunction "GND_GP") (pintype "power_in"))
      (node (ref "U$1") (pin "GP3") (pinfunction "COMMON_SW_GP3") (pintype "passive"))
      (node (ref "U1") (pin "12") (pinfunction "12_12") (pintype "bidirectional"))
      (node (ref "U1") (pin "GND@0") (pinfunction "GND_GND@0") (pintype "bidirectional"))
      (node (ref "U1") (pin "GND@1") (pinfunction "GND_GND@1") (pintype "bidirectional"))
      (node (ref "U1") (pin "GND@2") (pinfunction "GND_GND@2") (pintype "bidirectional"))
      (node (ref "U1") (pin "GND@3") (pinfunction "GND_GND@3") (pintype "bidirectional"))
      (node (ref "U1") (pin "GND@4") (pinfunction "GND_GND@4") (pintype "bidirectional"))
      (node (ref "U2") (pin "4") (pinfunction "GND_4") (pintype "bidirectional"))
      (node (ref "X1") (pin "2") (pinfunction "KL_2") (pintype "passive"))
      (node (ref "X1") (pin "4") (pinfunction "KL_4") (pintype "passive"))
    )
    (net (code "21") (name "Net-(A8B-1)") (class "Default")
      (node (ref "A8") (pin "2") (pinfunction "1_2") (pintype "passive"))
      (node (ref "U1") (pin "A8") (pinfunction "A8_A8") (pintype "bidirectional"))
    )
    (net (code "22") (name "Net-(A9B-1)") (class "Default")
      (node (ref "A9") (pin "2") (pinfunction "1_2") (pintype "passive"))
      (node (ref "U1") (pin "A9") (pinfunction "A9_A9") (pintype "bidirectional"))
    )
    (net (code "23") (name "Net-(A10B-1)") (class "Default")
      (node (ref "A10") (pin "2") (pinfunction "1_2") (pintype "passive"))
      (node (ref "U1") (pin "A10") (pinfunction "A10_A10") (pintype "bidirectional"))
    )
    (net (code "24") (name "Net-(A11B-1)") (class "Default")
      (node (ref "A11") (pin "2") (pinfunction "1_2") (pintype "passive"))
      (node (ref "U1") (pin "A11") (pinfunction "A11_A11") (pintype "bidirectional"))
    )
    (net (code "25") (name "Net-(A12B-1)") (class "Default")
      (node (ref "A12") (pin "2") (pinfunction "1_2") (pintype "passive"))
      (node (ref "U1") (pin "A12") (pinfunction "A12_A12") (pintype "bidirectional"))
    )
    (net (code "26") (name "Net-(A13B-1)") (class "Default")
      (node (ref "A13") (pin "2") (pinfunction "1_2") (pintype "passive"))
      (node (ref "U1") (pin "A13") (pinfunction "A13_A13") (pintype "bidirectional"))
    )
    (net (code "27") (name "Net-(A14B-1)") (class "Default")
      (node (ref "A14") (pin "2") (pinfunction "1_2") (pintype "passive"))
      (node (ref "U1") (pin "A14") (pinfunction "A14_A14") (pintype "bidirectional"))
    )
    (net (code "28") (name "Net-(A15B-1)") (class "Default")
      (node (ref "A15") (pin "2") (pinfunction "1_2") (pintype "passive"))
      (node (ref "U1") (pin "A15") (pinfunction "A15_A15") (pintype "bidirectional"))
    )
    (net (code "29") (name "Net-(C5-Pad1)") (class "Default")
      (node (ref "C5") (pin "1") (pinfunction "1_1") (pintype "passive"))
      (node (ref "R30") (pin "1") (pinfunction "1_1") (pintype "passive"))
      (node (ref "R31") (pin "1") (pinfunction "1_1") (pintype "passive"))
      (node (ref "R32") (pin "1") (pinfunction "1_1") (pintype "passive"))
    )
    (net (code "30") (name "Net-(C12-Pad1)") (class "Default")
      (node (ref "C12") (pin "1") (pinfunction "1_1") (pintype "passive"))
      (node (ref "R33") (pin "1") (pinfunction "1_1") (pintype "passive"))
    )
    (net (code "31") (name "Net-(D1-PadA)") (class "Default")
      (node (ref "D1") (pin "A") (pinfunction "A_A") (pintype "passive"))
      (node (ref "FS1") (pin "1") (pinfunction "1_1") (pintype "bidirectional"))
    )
    (net (code "32") (name "Net-(IC2-VBAT)") (class "Default")
      (node (ref "BATT1") (pin "V1") (pinfunction "V1_V1") (pintype "power_in"))
      (node (ref "BATT1") (pin "V2") (pinfunction "V2_V2") (pintype "power_in"))
      (node (ref "IC2") (pin "2") (pinfunction "VBAT_2") (pintype "power_in"))
    )
    (net (code "33") (name "Net-(IC2-X1)") (class "Default")
      (node (ref "IC2") (pin "3") (pinfunction "X1_3") (pintype "input"))
      (node (ref "Y1") (pin "2") (pinfunction "2_2") (pintype "passive"))
    )
    (net (code "34") (name "Net-(IC2-X2)") (class "Default")
      (node (ref "IC2") (pin "5") (pinfunction "X2_5") (pintype "output"))
      (node (ref "Y1") (pin "1") (pinfunction "1_1") (pintype "passive"))
    )
    (net (code "35") (name "Net-(IC2-{slash}INT0)") (class "Default")
      (node (ref "IC2") (pin "7") (pinfunction "/INT0_7") (pintype "output"))
      (node (ref "R1") (pin "1") (pinfunction "1_1") (pintype "passive"))
      (node (ref "U1") (pin "20") (pinfunction "20(SDA)_20") (pintype "bidirectional"))
    )
    (net (code "36") (name "Net-(LED1-PadC)") (class "Default")
      (node (ref "LED1") (pin "C") (pinfunction "C_C") (pintype "passive"))
      (node (ref "R19") (pin "2") (pinfunction "2_2") (pintype "passive"))
    )
    (net (code "37") (name "Net-(Q1-D)") (class "Default")
      (node (ref "A8") (pin "1") (pinfunction "1_1") (pintype "passive"))
      (node (ref "Q1") (pin "3") (pinfunction "D_3") (pintype "passive"))
    )
    (net (code "38") (name "Net-(Q1-S)") (class "Default")
      (node (ref "JP-A8") (pin "2") (pinfunction "2_2") (pintype "passive"))
      (node (ref "Q1") (pin "2") (pinfunction "S_2") (pintype "passive"))
      (node (ref "R2") (pin "2") (pinfunction "2_2") (pintype "passive"))
    )
    (net (code "39") (name "Net-(Q2-D)") (class "Default")
      (node (ref "A9") (pin "1") (pinfunction "1_1") (pintype "passive"))
      (node (ref "Q2") (pin "3") (pinfunction "D_3") (pintype "passive"))
    )
    (net (code "40") (name "Net-(Q2-S)") (class "Default")
      (node (ref "JP-A9") (pin "2") (pinfunction "2_2") (pintype "passive"))
      (node (ref "Q2") (pin "2") (pinfunction "S_2") (pintype "passive"))
      (node (ref "R10") (pin "2") (pinfunction "2_2") (pintype "passive"))
    )
    (net (code "41") (name "Net-(Q3-D)") (class "Default")
      (node (ref "A10") (pin "1") (pinfunction "1_1") (pintype "passive"))
      (node (ref "Q3") (pin "3") (pinfunction "D_3") (pintype "passive"))
    )
    (net (code "42") (name "Net-(Q3-S)") (class "Default")
      (node (ref "JP-A10") (pin "2") (pinfunction "2_2") (pintype "passive"))
      (node (ref "Q3") (pin "2") (pinfunction "S_2") (pintype "passive"))
      (node (ref "R3") (pin "2") (pinfunction "2_2") (pintype "passive"))
    )
    (net (code "43") (name "Net-(Q4-D)") (class "Default")
      (node (ref "A11") (pin "1") (pinfunction "1_1") (pintype "passive"))
      (node (ref "Q4") (pin "3") (pinfunction "D_3") (pintype "passive"))
    )
    (net (code "44") (name "Net-(Q4-S)") (class "Default")
      (node (ref "JP-A11") (pin "2") (pinfunction "2_2") (pintype "passive"))
      (node (ref "Q4") (pin "2") (pinfunction "S_2") (pintype "passive"))
      (node (ref "R4") (pin "2") (pinfunction "2_2") (pintype "passive"))
    )
    (net (code "45") (name "Net-(Q5-D)") (class "Default")
      (node (ref "A12") (pin "1") (pinfunction "1_1") (pintype "passive"))
      (node (ref "Q5") (pin "3") (pinfunction "D_3") (pintype "passive"))
    )
    (net (code "46") (name "Net-(Q5-S)") (class "Default")
      (node (ref "JP-A12") (pin "2") (pinfunction "2_2") (pintype "passive"))
      (node (ref "Q5") (pin "2") (pinfunction "S_2") (pintype "passive"))
      (node (ref "R6") (pin "2") (pinfunction "2_2") (pintype "passive"))
    )
    (net (code "47") (name "Net-(Q6-D)") (class "Default")
      (node (ref "A13") (pin "1") (pinfunction "1_1") (pintype "passive"))
      (node (ref "Q6") (pin "3") (pinfunction "D_3") (pintype "passive"))
    )
    (net (code "48") (name "Net-(Q6-S)") (class "Default")
      (node (ref "JP-A13") (pin "2") (pinfunction "2_2") (pintype "passive"))
      (node (ref "Q6") (pin "2") (pinfunction "S_2") (pintype "passive"))
      (node (ref "R7") (pin "2") (pinfunction "2_2") (pintype "passive"))
    )
    (net (code "49") (name "Net-(Q7-D)") (class "Default")
      (node (ref "A14") (pin "1") (pinfunction "1_1") (pintype "passive"))
      (node (ref "Q7") (pin "3") (pinfunction "D_3") (pintype "passive"))
    )
    (net (code "50") (name "Net-(Q7-S)") (class "Default")
      (node (ref "JP-A14") (pin "2") (pinfunction "2_2") (pintype "passive"))
      (node (ref "Q7") (pin "2") (pinfunction "S_2") (pintype "passive"))
      (node (ref "R8") (pin "2") (pinfunction "2_2") (pintype "passive"))
    )
    (net (code "51") (name "Net-(Q8-D)") (class "Default")
      (node (ref "A15") (pin "1") (pinfunction "1_1") (pintype "passive"))
      (node (ref "Q8") (pin "3") (pinfunction "D_3") (pintype "passive"))
    )
    (net (code "52") (name "Net-(Q8-S)") (class "Default")
      (node (ref "JP-A15") (pin "2") (pinfunction "2_2") (pintype "passive"))
      (node (ref "Q8") (pin "2") (pinfunction "S_2") (pintype "passive"))
      (node (ref "R9") (pin "2") (pinfunction "2_2") (pintype "passive"))
    )
    (net (code "53") (name "Net-(Q9-B)") (class "Default")
      (node (ref "Q9") (pin "1") (pinfunction "B_1") (pintype "passive"))
      (node (ref "R11") (pin "1") (pinfunction "1_1") (pintype "passive"))
    )
    (net (code "54") (name "Net-(Q10-B)") (class "Default")
      (node (ref "Q10") (pin "1") (pinfunction "B_1") (pintype "passive"))
      (node (ref "R12") (pin "2") (pinfunction "2_2") (pintype "passive"))
    )
    (net (code "55") (name "Net-(Q11-B)") (class "Default")
      (node (ref "Q11") (pin "1") (pinfunction "B_1") (pintype "passive"))
      (node (ref "R13") (pin "2") (pinfunction "2_2") (pintype "passive"))
    )
    (net (code "56") (name "Net-(Q12-B)") (class "Default")
      (node (ref "Q12") (pin "1") (pinfunction "B_1") (pintype "passive"))
      (node (ref "R14") (pin "2") (pinfunction "2_2") (pintype "passive"))
    )
    (net (code "57") (name "Net-(Q13-B)") (class "Default")
      (node (ref "Q13") (pin "1") (pinfunction "B_1") (pintype "passive"))
      (node (ref "R15") (pin "2") (pinfunction "2_2") (pintype "passive"))
    )
    (net (code "58") (name "Net-(Q14-B)") (class "Default")
      (node (ref "Q14") (pin "1") (pinfunction "B_1") (pintype "passive"))
      (node (ref "R16") (pin "2") (pinfunction "2_2") (pintype "passive"))
    )
    (net (code "59") (name "Net-(Q15-B)") (class "Default")
      (node (ref "Q15") (pin "1") (pinfunction "B_1") (pintype "passive"))
      (node (ref "R17") (pin "2") (pinfunction "2_2") (pintype "passive"))
    )
    (net (code "60") (name "Net-(Q16-B)") (class "Default")
      (node (ref "Q16") (pin "1") (pinfunction "B_1") (pintype "passive"))
      (node (ref "R18") (pin "2") (pinfunction "2_2") (pintype "passive"))
    )
    (net (code "61") (name "Net-(Q17-D)") (class "Default")
      (node (ref "Q17") (pin "3") (pinfunction "D_3") (pintype "passive"))
      (node (ref "SER1") (pin "1") (pinfunction "1_1") (pintype "passive"))
    )
    (net (code "62") (name "Net-(Q17-G)") (class "Default")
      (node (ref "Q17") (pin "1") (pinfunction "G_1") (pintype "passive"))
      (node (ref "Q22") (pin "3") (pinfunction "C_3") (pintype "passive"))
      (node (ref "R20") (pin "2") (pinfunction "2_2") (pintype "passive"))
    )
    (net (code "63") (name "Net-(Q17-S)") (class "Default")
      (node (ref "JP-S1") (pin "2") (pinfunction "2_2") (pintype "passive"))
      (node (ref "Q17") (pin "2") (pinfunction "S_2") (pintype "passive"))
      (node (ref "R20") (pin "1") (pinfunction "1_1") (pintype "passive"))
    )
    (net (code "64") (name "Net-(Q18-D)") (class "Default")
      (node (ref "Q18") (pin "3") (pinfunction "D_3") (pintype "passive"))
      (node (ref "SER2") (pin "1") (pinfunction "1_1") (pintype "passive"))
    )
    (net (code "65") (name "Net-(Q18-G)") (class "Default")
      (node (ref "Q18") (pin "1") (pinfunction "G_1") (pintype "passive"))
      (node (ref "Q21") (pin "3") (pinfunction "C_3") (pintype "passive"))
      (node (ref "R21") (pin "2") (pinfunction "2_2") (pintype "passive"))
    )
    (net (code "66") (name "Net-(Q18-S)") (class "Default")
      (node (ref "JP-S2") (pin "2") (pinfunction "2_2") (pintype "passive"))
      (node (ref "Q18") (pin "2") (pinfunction "S_2") (pintype "passive"))
      (node (ref "R21") (pin "1") (pinfunction "1_1") (pintype "passive"))
    )
    (net (code "67") (name "Net-(Q19-D)") (class "Default")
      (node (ref "Q19") (pin "3") (pinfunction "D_3") (pintype "passive"))
      (node (ref "SER3") (pin "1") (pinfunction "1_1") (pintype "passive"))
    )
    (net (code "68") (name "Net-(Q19-G)") (class "Default")
      (node (ref "Q19") (pin "1") (pinfunction "G_1") (pintype "passive"))
      (node (ref "Q20") (pin "3") (pinfunction "C_3") (pintype "passive"))
      (node (ref "R22") (pin "2") (pinfunction "2_2") (pintype "passive"))
    )
    (net (code "69") (name "Net-(Q19-S)") (class "Default")
      (node (ref "JP-S3") (pin "2") (pinfunction "2_2") (pintype "passive"))
      (node (ref "Q19") (pin "2") (pinfunction "S_2") (pintype "passive"))
      (node (ref "R22") (pin "1") (pinfunction "1_1") (pintype "passive"))
    )
    (net (code "70") (name "Net-(Q20-B)") (class "Default")
      (node (ref "Q20") (pin "1") (pinfunction "B_1") (pintype "passive"))
      (node (ref "R26") (pin "1") (pinfunction "1_1") (pintype "passive"))
    )
    (net (code "71") (name "Net-(Q21-B)") (class "Default")
      (node (ref "Q21") (pin "1") (pinfunction "B_1") (pintype "passive"))
      (node (ref "R27") (pin "1") (pinfunction "1_1") (pintype "passive"))
    )
    (net (code "72") (name "Net-(Q22-B)") (class "Default")
      (node (ref "Q22") (pin "1") (pinfunction "B_1") (pintype "passive"))
      (node (ref "R28") (pin "1") (pinfunction "1_1") (pintype "passive"))
    )
    (net (code "73") (name "Net-(R11-Pad2)") (class "Default")
      (node (ref "R11") (pin "2") (pinfunction "2_2") (pintype "passive"))
      (node (ref "U1") (pin "47") (pinfunction "47_47") (pintype "bidirectional"))
    )
    (net (code "74") (name "Net-(R12-Pad1)") (class "Default")
      (node (ref "R12") (pin "1") (pinfunction "1_1") (pintype "passive"))
      (node (ref "U1") (pin "46") (pinfunction "46_46") (pintype "bidirectional"))
    )
    (net (code "75") (name "Net-(R13-Pad1)") (class "Default")
      (node (ref "R13") (pin "1") (pinfunction "1_1") (pintype "passive"))
      (node (ref "U1") (pin "45") (pinfunction "45_45") (pintype "bidirectional"))
    )
    (net (code "76") (name "Net-(R14-Pad1)") (class "Default")
      (node (ref "R14") (pin "1") (pinfunction "1_1") (pintype "passive"))
      (node (ref "U1") (pin "44") (pinfunction "44_44") (pintype "bidirectional"))
    )
    (net (code "77") (name "Net-(R15-Pad1)") (class "Default")
      (node (ref "R15") (pin "1") (pinfunction "1_1") (pintype "passive"))
      (node (ref "U1") (pin "43") (pinfunction "43_43") (pintype "bidirectional"))
    )
    (net (code "78") (name "Net-(R16-Pad1)") (class "Default")
      (node (ref "R16") (pin "1") (pinfunction "1_1") (pintype "passive"))
      (node (ref "U1") (pin "42") (pinfunction "42_42") (pintype "bidirectional"))
    )
    (net (code "79") (name "Net-(R17-Pad1)") (class "Default")
      (node (ref "R17") (pin "1") (pinfunction "1_1") (pintype "passive"))
      (node (ref "U1") (pin "41") (pinfunction "41_41") (pintype "bidirectional"))
    )
    (net (code "80") (name "Net-(R18-Pad1)") (class "Default")
      (node (ref "R18") (pin "1") (pinfunction "1_1") (pintype "passive"))
      (node (ref "U1") (pin "40") (pinfunction "40_40") (pintype "bidirectional"))
    )
    (net (code "81") (name "Net-(R26-Pad2)") (class "Default")
      (node (ref "R26") (pin "2") (pinfunction "2_2") (pintype "passive"))
      (node (ref "U1") (pin "24") (pinfunction "24_24") (pintype "bidirectional"))
    )
    (net (code "82") (name "Net-(R27-Pad2)") (class "Default")
      (node (ref "R27") (pin "2") (pinfunction "2_2") (pintype "passive"))
      (node (ref "U1") (pin "23") (pinfunction "23_23") (pintype "bidirectional"))
    )
    (net (code "83") (name "Net-(R28-Pad2)") (class "Default")
      (node (ref "R28") (pin "2") (pinfunction "2_2") (pintype "passive"))
      (node (ref "U1") (pin "22") (pinfunction "22_22") (pintype "bidirectional"))
    )
    (net (code "84") (name "Net-(RESET-1)") (class "Default")
      (node (ref "RESET") (pin "P$1") (pinfunction "1_P$1") (pintype "passive"))
      (node (ref "U1") (pin "RESET") (pinfunction "RESET_RESET") (pintype "bidirectional"))
    )
    (net (code "85") (name "Net-(SER1B-1)") (class "Default")
      (node (ref "SER1") (pin "2") (pinfunction "1_2") (pintype "passive"))
      (node (ref "U1") (pin "19") (pinfunction "19(RX1)_19") (pintype "bidirectional"))
    )
    (net (code "86") (name "Net-(SER1C-1)") (class "Default")
      (node (ref "SER1") (pin "3") (pinfunction "1_3") (pintype "passive"))
      (node (ref "U1") (pin "18") (pinfunction "18(TX1)_18") (pintype "bidirectional"))
    )
    (net (code "87") (name "Net-(SER2B-1)") (class "Default")
      (node (ref "SER2") (pin "2") (pinfunction "1_2") (pintype "passive"))
      (node (ref "U1") (pin "17") (pinfunction "17(RX2)_17") (pintype "bidirectional"))
    )
    (net (code "88") (name "Net-(SER2C-1)") (class "Default")
      (node (ref "SER2") (pin "3") (pinfunction "1_3") (pintype "passive"))
      (node (ref "U1") (pin "16") (pinfunction "16(TX2)_16") (pintype "bidirectional"))
    )
    (net (code "89") (name "Net-(SER3B-1)") (class "Default")
      (node (ref "SER3") (pin "2") (pinfunction "1_2") (pintype "passive"))
      (node (ref "SJ2") (pin "2") (pinfunction "2_2") (pintype "passive"))
      (node (ref "U1") (pin "15") (pinfunction "15(RX3)_15") (pintype "bidirectional"))
    )
    (net (code "90") (name "Net-(SER3C-1)") (class "Default")
      (node (ref "SER3") (pin "3") (pinfunction "1_3") (pintype "passive"))
      (node (ref "SJ1") (pin "2") (pinfunction "2_2") (pintype "passive"))
      (node (ref "U1") (pin "14") (pinfunction "14(TX3)_14") (pintype "bidirectional"))
    )
    (net (code "91") (name "Net-(SJ1-Pad1)") (class "Default")
      (node (ref "SJ1") (pin "1") (pinfunction "1_1") (pintype "passive"))
      (node (ref "U1") (pin "2") (pinfunction "2_2") (pintype "bidirectional"))
    )
    (net (code "92") (name "Net-(SJ2-Pad1)") (class "Default")
      (node (ref "SJ2") (pin "1") (pinfunction "1_1") (pintype "passive"))
      (node (ref "U1") (pin "3") (pinfunction "3_3") (pintype "bidirectional"))
    )
    (net (code "93") (name "Net-(U2-BS)") (class "Default")
      (node (ref "R33") (pin "2") (pinfunction "2_2") (pintype "passive"))
      (node (ref "U2") (pin "5") (pinfunction "BS_5") (pintype "bidirectional"))
    )
    (net (code "94") (name "Net-(U2-EN{slash}SYNC)") (class "Default")
      (node (ref "R29") (pin "1") (pinfunction "1_1") (pintype "passive"))
      (node (ref "U2") (pin "6") (pinfunction "EN/SYNC_6") (pintype "bidirectional"))
    )
    (net (code "95") (name "Net-(U2-FB)") (class "Default")
      (node (ref "R30") (pin "2") (pinfunction "2_2") (pintype "passive"))
      (node (ref "U2") (pin "8") (pinfunction "FB_8") (pintype "bidirectional"))
    )
    (net (code "96") (name "Net-(U2-SS)") (class "Default")
      (node (ref "C11") (pin "1") (pinfunction "1_1") (pintype "passive"))
      (node (ref "U2") (pin "1") (pinfunction "SS_1") (pintype "bidirectional"))
    )
    (net (code "97") (name "Net-(U2-SW)") (class "Default")
      (node (ref "C12") (pin "2") (pinfunction "2_2") (pintype "passive"))
      (node (ref "L2") (pin "1") (pinfunction "1_1") (pintype "passive"))
      (node (ref "U2") (pin "3") (pinfunction "SW_3") (pintype "bidirectional"))
    )
    (net (code "98") (name "Net-(U2-VCC)") (class "Default")
      (node (ref "C10") (pin "1") (pinfunction "1_1") (pintype "passive"))
      (node (ref "U2") (pin "7") (pinfunction "VCC_7") (pintype "bidirectional"))
    )
    (net (code "99") (name "Net-(X1A-KL)") (class "Default")
      (node (ref "FS2") (pin "2") (pinfunction "2_2") (pintype "bidirectional"))
      (node (ref "X1") (pin "1") (pinfunction "KL_1") (pintype "passive"))
    )
    (net (code "100") (name "Net-(X1C-KL)") (class "Default")
      (node (ref "FS1") (pin "2") (pinfunction "2_2") (pintype "bidirectional"))
      (node (ref "FS2") (pin "1") (pinfunction "1_1") (pintype "bidirectional"))
      (node (ref "X1") (pin "3") (pinfunction "KL_3") (pintype "passive"))
    )
    (net (code "101") (name "unconnected-(IC1-OUT-Pad4)") (class "Default")
      (node (ref "IC1") (pin "4") (pinfunction "OUT_4") (pintype "output"))
    )
    (net (code "102") (name "unconnected-(IC2-1HZ-Pad9)") (class "Default")
      (node (ref "IC2") (pin "9") (pinfunction "1HZ_9") (pintype "output"))
    )
    (net (code "103") (name "unconnected-(IC2-32KHZ-Pad18)") (class "Default")
      (node (ref "IC2") (pin "18") (pinfunction "32KHZ_18") (pintype "output"))
    )
    (net (code "104") (name "unconnected-(IC2-INT1-Pad8)") (class "Default")
      (node (ref "IC2") (pin "8") (pinfunction "INT1_8") (pintype "output"))
    )
    (net (code "105") (name "unconnected-(IC3D-O-Pad11)") (class "Default")
      (node (ref "IC3") (pin "11") (pinfunction "O_11") (pintype "tri_state"))
    )
    (net (code "106") (name "unconnected-(U$1-CARD_DETECT-PadCD)") (class "Default")
      (node (ref "U$1") (pin "CD") (pinfunction "CARD_DETECT_CD") (pintype "passive"))
    )
    (net (code "107") (name "unconnected-(U$1-DAT1-Pad8)") (class "Default")
      (node (ref "U$1") (pin "8") (pinfunction "DAT1_8") (pintype "bidirectional"))
    )
    (net (code "108") (name "unconnected-(U$1-DAT2-Pad9)") (class "Default")
      (node (ref "U$1") (pin "9") (pinfunction "DAT2_9") (pintype "bidirectional"))
    )
    (net (code "109") (name "unconnected-(U$1-WRITE_PROTECT-PadWP)") (class "Default")
      (node (ref "U$1") (pin "WP") (pinfunction "WRITE_PROTECT_WP") (pintype "passive"))
    )
    (net (code "110") (name "unconnected-(U1-0(RX0)-Pad0)") (class "Default")
      (node (ref "U1") (pin "0") (pinfunction "0(RX0)_0") (pintype "bidirectional"))
    )
    (net (code "111") (name "unconnected-(U1-1(TX0)-Pad1)") (class "Default")
      (node (ref "U1") (pin "1") (pinfunction "1(TX0)_1") (pintype "bidirectional"))
    )
    (net (code "112") (name "unconnected-(U1-21(SCL)-Pad21)") (class "Default")
      (node (ref "U1") (pin "21") (pinfunction "21(SCL)_21") (pintype "bidirectional"))
    )
    (net (code "113") (name "unconnected-(U1-A0(RX0)-PadA0)") (class "Default")
      (node (ref "U1") (pin "A0") (pinfunction "A0(RX0)_A0") (pintype "bidirectional"))
    )
    (net (code "114") (name "unconnected-(U1-A1(TX0)-PadA1)") (class "Default")
      (node (ref "U1") (pin "A1") (pinfunction "A1(TX0)_A1") (pintype "bidirectional"))
    )
    (net (code "115") (name "unconnected-(U1-Pad3.3V)") (class "Default")
      (node (ref "U1") (pin "3.3V") (pinfunction "3.3V_3.3V") (pintype "bidirectional"))
    )
    (net (code "116") (name "unconnected-(U1-Pad4)") (class "Default")
      (node (ref "U1") (pin "4") (pinfunction "4_4") (pintype "bidirectional"))
    )
    (net (code "117") (name "unconnected-(U1-Pad5)") (class "Default")
      (node (ref "U1") (pin "5") (pinfunction "5_5") (pintype "bidirectional"))
    )
    (net (code "118") (name "unconnected-(U1-Pad6)") (class "Default")
      (node (ref "U1") (pin "6") (pinfunction "6_6") (pintype "bidirectional"))
    )
    (net (code "119") (name "unconnected-(U1-Pad7)") (class "Default")
      (node (ref "U1") (pin "7") (pinfunction "7_7") (pintype "bidirectional"))
    )
    (net (code "120") (name "unconnected-(U1-Pad8)") (class "Default")
      (node (ref "U1") (pin "8") (pinfunction "8_8") (pintype "bidirectional"))
    )
    (net (code "121") (name "unconnected-(U1-Pad9)") (class "Default")
      (node (ref "U1") (pin "9") (pinfunction "9_9") (pintype "bidirectional"))
    )
    (net (code "122") (name "unconnected-(U1-Pad10)") (class "Default")
      (node (ref "U1") (pin "10") (pinfunction "10_10") (pintype "bidirectional"))
    )
    (net (code "123") (name "unconnected-(U1-Pad11)") (class "Default")
      (node (ref "U1") (pin "11") (pinfunction "11_11") (pintype "bidirectional"))
    )
    (net (code "124") (name "unconnected-(U1-Pad13)") (class "Default")
      (node (ref "U1") (pin "13") (pinfunction "13_13") (pintype "bidirectional"))
    )
    (net (code "125") (name "unconnected-(U1-Pad25)") (class "Default")
      (node (ref "U1") (pin "25") (pinfunction "25_25") (pintype "bidirectional"))
    )
    (net (code "126") (name "unconnected-(U1-Pad26)") (class "Default")
      (node (ref "U1") (pin "26") (pinfunction "26_26") (pintype "bidirectional"))
    )
    (net (code "127") (name "unconnected-(U1-Pad27)") (class "Default")
      (node (ref "U1") (pin "27") (pinfunction "27_27") (pintype "bidirectional"))
    )
    (net (code "128") (name "unconnected-(U1-Pad28)") (class "Default")
      (node (ref "U1") (pin "28") (pinfunction "28_28") (pintype "bidirectional"))
    )
    (net (code "129") (name "unconnected-(U1-Pad29)") (class "Default")
      (node (ref "U1") (pin "29") (pinfunction "29_29") (pintype "bidirectional"))
    )
    (net (code "130") (name "unconnected-(U1-Pad30)") (class "Default")
      (node (ref "U1") (pin "30") (pinfunction "30_30") (pintype "bidirectional"))
    )
    (net (code "131") (name "unconnected-(U1-Pad31)") (class "Default")
      (node (ref "U1") (pin "31") (pinfunction "31_31") (pintype "bidirectional"))
    )
    (net (code "132") (name "unconnected-(U1-Pad32)") (class "Default")
      (node (ref "U1") (pin "32") (pinfunction "32_32") (pintype "bidirectional"))
    )
    (net (code "133") (name "unconnected-(U1-Pad33)") (class "Default")
      (node (ref "U1") (pin "33") (pinfunction "33_33") (pintype "bidirectional"))
    )
    (net (code "134") (name "unconnected-(U1-Pad34)") (class "Default")
      (node (ref "U1") (pin "34") (pinfunction "34_34") (pintype "bidirectional"))
    )
    (net (code "135") (name "unconnected-(U1-Pad35)") (class "Default")
      (node (ref "U1") (pin "35") (pinfunction "35_35") (pintype "bidirectional"))
    )
    (net (code "136") (name "unconnected-(U1-Pad36)") (class "Default")
      (node (ref "U1") (pin "36") (pinfunction "36_36") (pintype "bidirectional"))
    )
    (net (code "137") (name "unconnected-(U1-Pad37)") (class "Default")
      (node (ref "U1") (pin "37") (pinfunction "37_37") (pintype "bidirectional"))
    )
    (net (code "138") (name "unconnected-(U1-Pad38)") (class "Default")
      (node (ref "U1") (pin "38") (pinfunction "38_38") (pintype "bidirectional"))
    )
    (net (code "139") (name "unconnected-(U1-Pad39)") (class "Default")
      (node (ref "U1") (pin "39") (pinfunction "39_39") (pintype "bidirectional"))
    )
    (net (code "140") (name "unconnected-(U1-Pad53)") (class "Default")
      (node (ref "U1") (pin "53") (pinfunction "53_53") (pintype "bidirectional"))
    )
    (net (code "141") (name "unconnected-(U1-PadA2)") (class "Default")
      (node (ref "U1") (pin "A2") (pinfunction "A2_A2") (pintype "bidirectional"))
    )
    (net (code "142") (name "unconnected-(U1-PadA3)") (class "Default")
      (node (ref "U1") (pin "A3") (pinfunction "A3_A3") (pintype "bidirectional"))
    )
    (net (code "143") (name "unconnected-(U1-PadA4)") (class "Default")
      (node (ref "U1") (pin "A4") (pinfunction "A4_A4") (pintype "bidirectional"))
    )
    (net (code "144") (name "unconnected-(U1-PadA5)") (class "Default")
      (node (ref "U1") (pin "A5") (pinfunction "A5_A5") (pintype "bidirectional"))
    )
    (net (code "145") (name "unconnected-(U1-PadA6)") (class "Default")
      (node (ref "U1") (pin "A6") (pinfunction "A6_A6") (pintype "bidirectional"))
    )
    (net (code "146") (name "unconnected-(U1-PadA7)") (class "Default")
      (node (ref "U1") (pin "A7") (pinfunction "A7_A7") (pintype "bidirectional"))
    )
    (net (code "147") (name "unconnected-(U1-PadAREF)") (class "Default")
      (node (ref "U1") (pin "AREF") (pinfunction "AREF_AREF") (pintype "bidirectional"))
    )
    (net (code "148") (name "unconnected-(U1-PadVIN)") (class "Default")
      (node (ref "U1") (pin "VIN") (pinfunction "VIN_VIN") (pintype "bidirectional"))
    )
  )
)
